# LV_cutoff.net
KiCad netlist of a schematic drawn in EAGLE
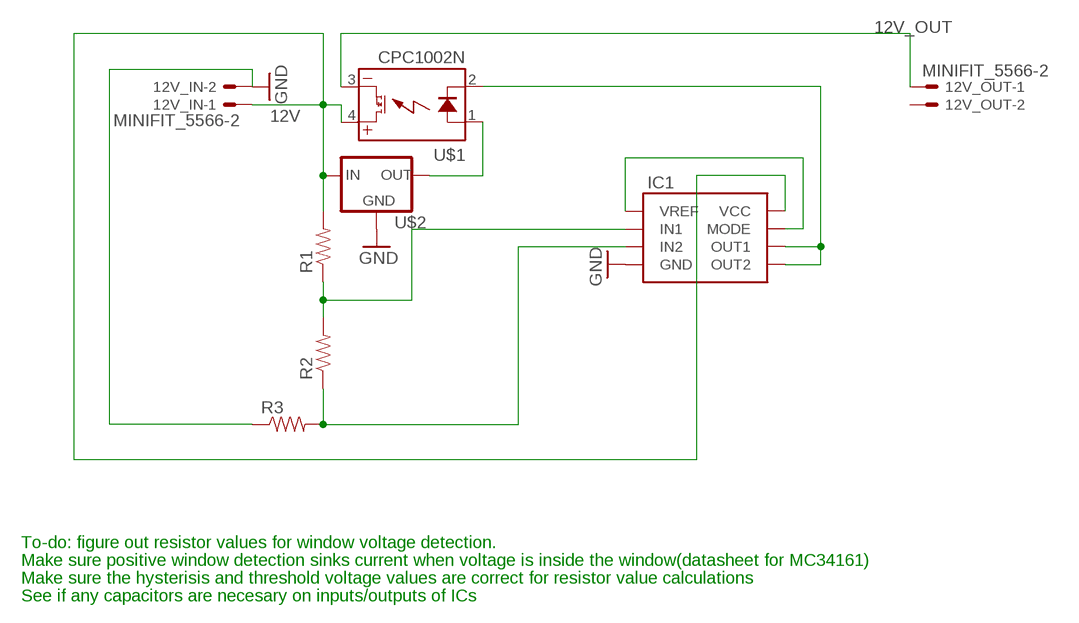
[diagram p0: schematic, sheet 1]

(export (version "E")
  (design (tool "Eeschema 10.0.6"))
  (components
    (comp (ref "12V_IN")
      (value "MINIFIT_5566-2")
      (footprint "eagle-import:MINIFIT_5566-2")
      (libsource (lib "eagle-import") (part "MINIFIT_5566-2"))
    )
    (comp (ref "12V_OUT")
      (value "MINIFIT_5566-2")
      (footprint "eagle-import:MINIFIT_5566-2")
      (libsource (lib "eagle-import") (part "MINIFIT_5566-2"))
    )
    (comp (ref "IC1")
      (value "MC34161DG")
      (footprint "eagle-import:SOIC-08")
      (libsource (lib "eagle-import") (part "MC34161DG"))
    )
    (comp (ref "R1")
      (value "RESISTOR0805-RES")
      (footprint "eagle-import:0805")
      (libsource (lib "eagle-import") (part "RESISTOR0805-RES"))
    )
    (comp (ref "R2")
      (value "RESISTOR0805-RES")
      (footprint "eagle-import:0805")
      (libsource (lib "eagle-import") (part "RESISTOR0805-RES"))
    )
    (comp (ref "R3")
      (value "RESISTOR0805-RES")
      (footprint "eagle-import:0805")
      (libsource (lib "eagle-import") (part "RESISTOR0805-RES"))
    )
    (comp (ref "U$1")
      (value "CPC1002N")
      (footprint "eagle-import:SOP04")
      (libsource (lib "eagle-import") (part "CPC1002N"))
    )
    (comp (ref "U$2")
      (value "5VREG_LM340-NLM340MPX-5.0/NOPB")
      (footprint "eagle-import:SOT223")
      (libsource (lib "eagle-import") (part "5VREG_LM340-NLM340MPX-5.0/NOPB"))
    )
  )
  (nets
    (net (code "1") (name "/12V") (class "Default")
      (node (ref "12V_IN") (pin "1") (pinfunction "S_1") (pintype "passive"))
      (node (ref "IC1") (pin "8") (pinfunction "VCC_8") (pintype "passive"))
      (node (ref "R1") (pin "2") (pinfunction "2_2") (pintype "passive"))
      (node (ref "U$1") (pin "4") (pinfunction "DC+_4") (pintype "passive"))
      (node (ref "U$2") (pin "1") (pinfunction "IN_1") (pintype "input"))
    )
    (net (code "2") (name "/12V_OUT") (class "Default")
      (node (ref "12V_OUT") (pin "1") (pinfunction "S_1") (pintype "passive"))
      (node (ref "U$1") (pin "3") (pinfunction "DC-_3") (pintype "passive"))
    )
    (net (code "3") (name "GND") (class "Default")
      (node (ref "12V_IN") (pin "2") (pinfunction "S_2") (pintype "passive"))
      (node (ref "IC1") (pin "4") (pinfunction "GND_4") (pintype "passive"))
      (node (ref "R3") (pin "1") (pinfunction "1_1") (pintype "passive"))
      (node (ref "U$2") (pin "2") (pinfunction "GND_2") (pintype "input"))
      (node (ref "U$2") (pin "4") (pinfunction "GND_4") (pintype "input"))
    )
    (net (code "4") (name "Net-(IC1-IN1)") (class "Default")
      (node (ref "IC1") (pin "2") (pinfunction "IN1_2") (pintype "passive"))
      (node (ref "R1") (pin "1") (pinfunction "1_1") (pintype "passive"))
      (node (ref "R2") (pin "2") (pinfunction "2_2") (pintype "passive"))
    )
    (net (code "5") (name "Net-(IC1-IN2)") (class "Default")
      (node (ref "IC1") (pin "3") (pinfunction "IN2_3") (pintype "passive"))
      (node (ref "R2") (pin "1") (pinfunction "1_1") (pintype "passive"))
      (node (ref "R3") (pin "2") (pinfunction "2_2") (pintype "passive"))
    )
    (net (code "6") (name "Net-(IC1-MODE)") (class "Default")
      (node (ref "IC1") (pin "1") (pinfunction "VREF_1") (pintype "passive"))
      (node (ref "IC1") (pin "7") (pinfunction "MODE_7") (pintype "passive"))
    )
    (net (code "7") (name "Net-(IC1-OUT1)") (class "Default")
      (node (ref "IC1") (pin "5") (pinfunction "OUT2_5") (pintype "passive"))
      (node (ref "IC1") (pin "6") (pinfunction "OUT1_6") (pintype "passive"))
      (node (ref "U$1") (pin "2") (pinfunction "CONTROL-_2") (pintype "passive"))
    )
    (net (code "8") (name "Net-(U$1-CONTROL+)") (class "Default")
      (node (ref "U$1") (pin "1") (pinfunction "CONTROL+_1") (pintype "passive"))
      (node (ref "U$2") (pin "3") (pinfunction "OUT_3") (pintype "output"))
    )
    (net (code "9") (name "unconnected-(12V_OUTB-S-Pad2)") (class "Default")
      (node (ref "12V_OUT") (pin "2") (pinfunction "S_2") (pintype "passive"))
    )
  )
)
